# design-1v1.net
KiCad netlist of a schematic drawn in EAGLE
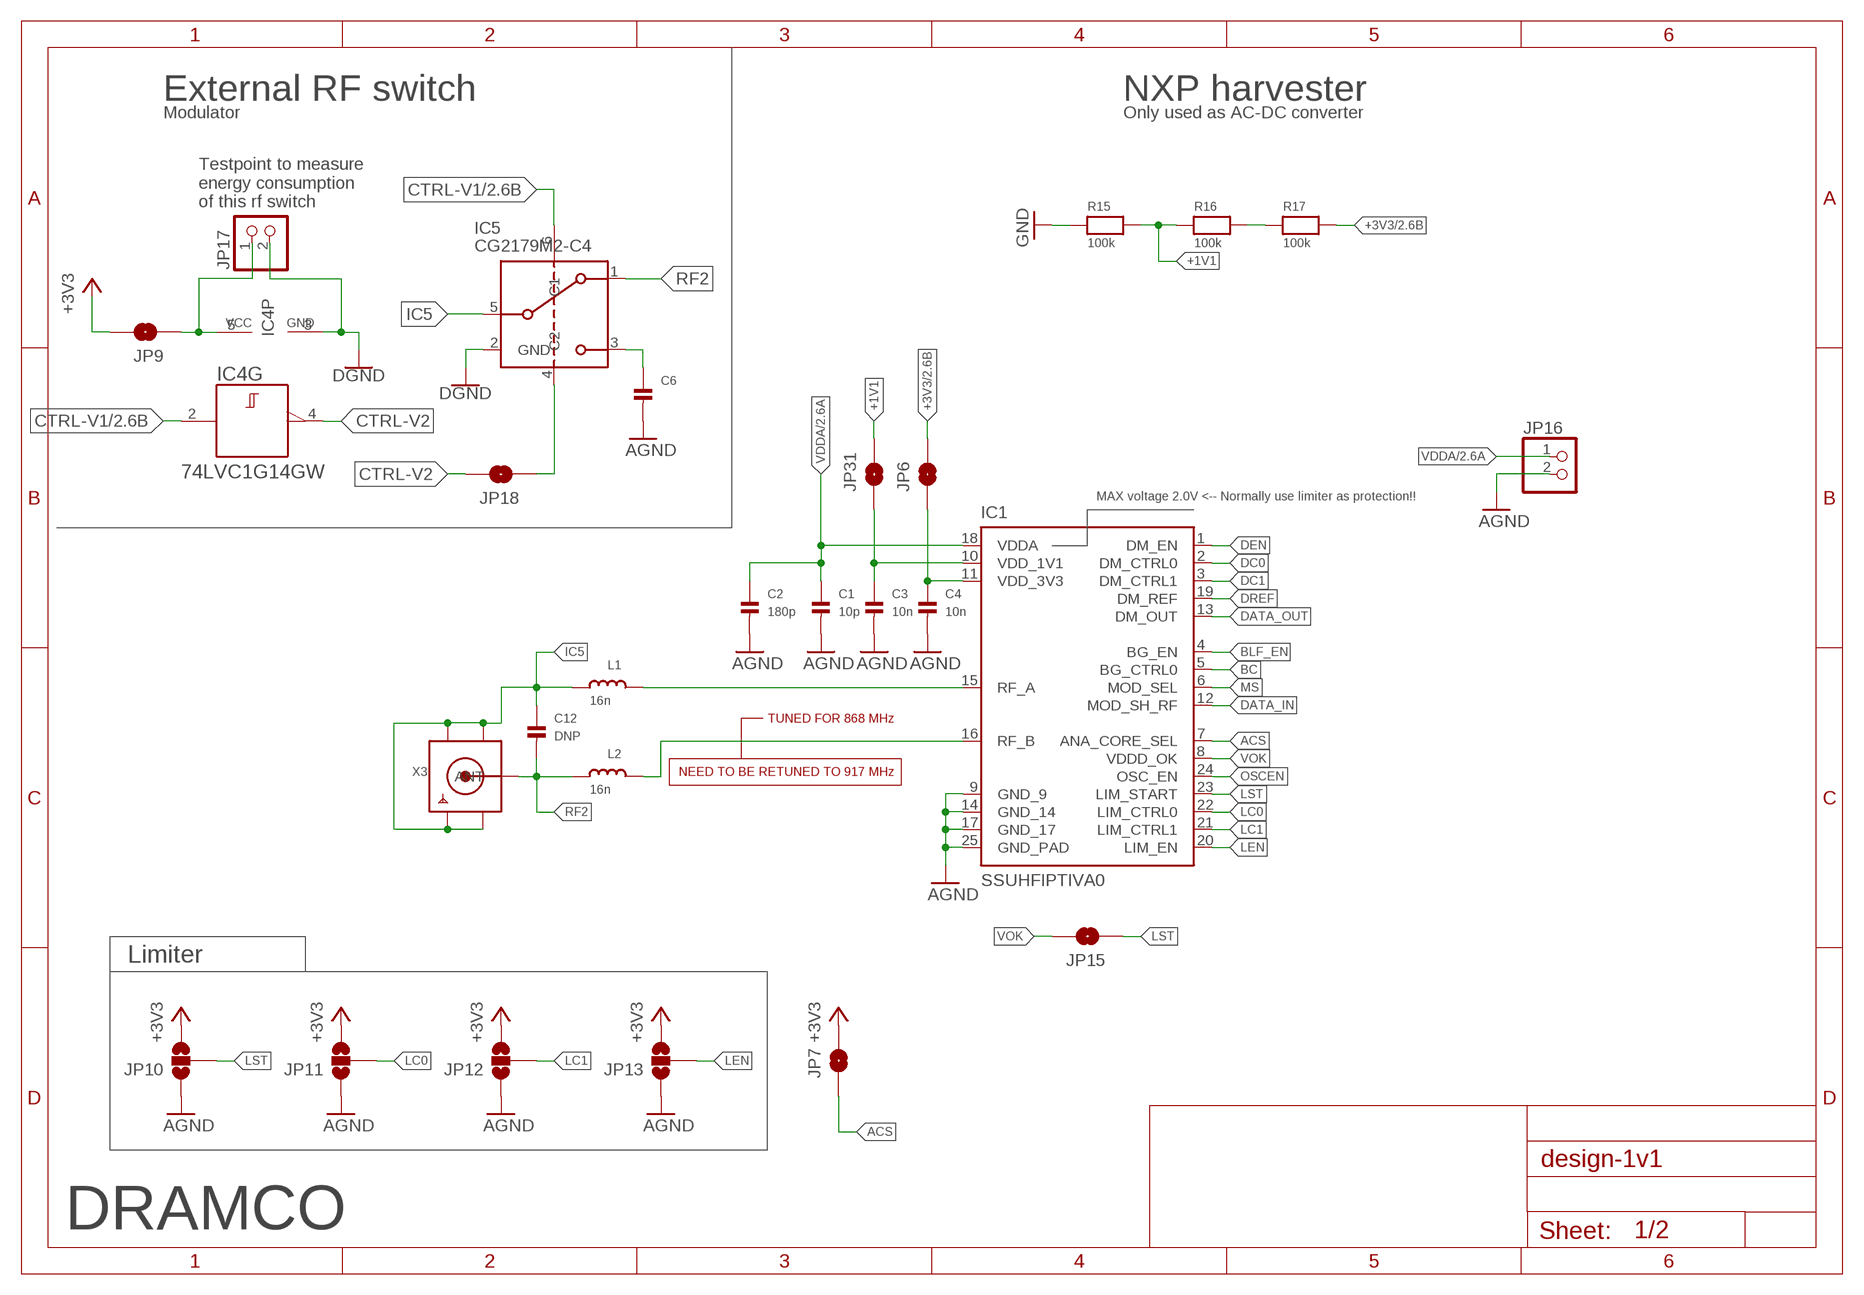
[diagram p0: schematic, sheet 1]
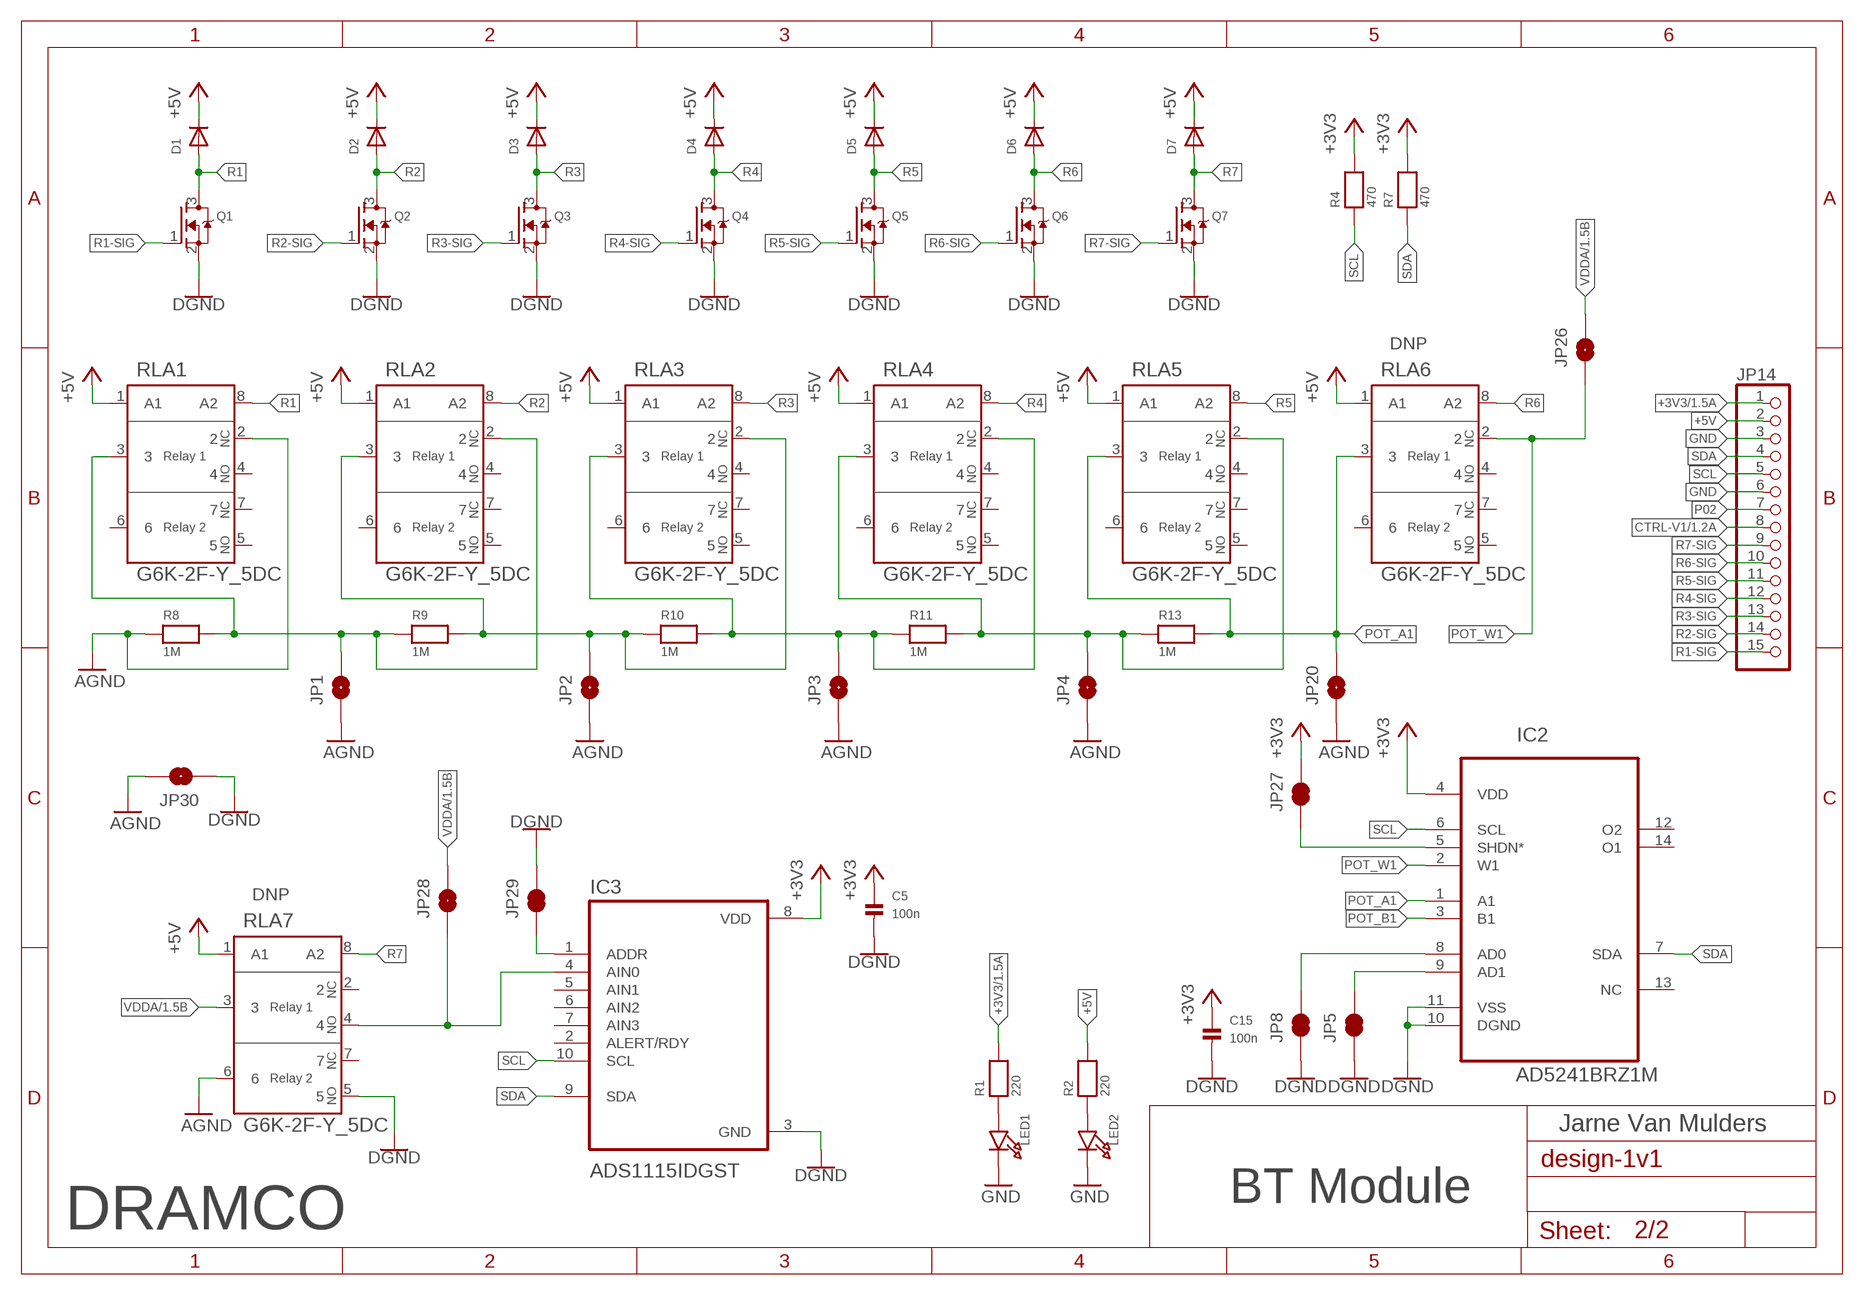
[diagram p1: schematic, sheet 2]

(export (version "E")
  (design (tool "Eeschema 10.0.6"))
  (components
    (comp (ref "C5")
      (value "100n")
      (footprint "eagle-import:0603")
      (libsource (lib "eagle-import") (part "CAP_CERAMIC0603"))
    )
    (comp (ref "C15")
      (value "100n")
      (footprint "eagle-import:0603")
      (libsource (lib "eagle-import") (part "CAP_CERAMIC0603"))
    )
    (comp (ref "D1")
      (value "DIODESOD-123")
      (footprint "eagle-import:SOD-123")
      (libsource (lib "eagle-import") (part "DIODESOD-123"))
    )
    (comp (ref "D2")
      (value "DIODESOD-123")
      (footprint "eagle-import:SOD-123")
      (libsource (lib "eagle-import") (part "DIODESOD-123"))
    )
    (comp (ref "D3")
      (value "DIODESOD-123")
      (footprint "eagle-import:SOD-123")
      (libsource (lib "eagle-import") (part "DIODESOD-123"))
    )
    (comp (ref "D4")
      (value "DIODESOD-123")
      (footprint "eagle-import:SOD-123")
      (libsource (lib "eagle-import") (part "DIODESOD-123"))
    )
    (comp (ref "D5")
      (value "DIODESOD-123")
      (footprint "eagle-import:SOD-123")
      (libsource (lib "eagle-import") (part "DIODESOD-123"))
    )
    (comp (ref "D6")
      (value "DIODESOD-123")
      (footprint "eagle-import:SOD-123")
      (libsource (lib "eagle-import") (part "DIODESOD-123"))
    )
    (comp (ref "D7")
      (value "DIODESOD-123")
      (footprint "eagle-import:SOD-123")
      (libsource (lib "eagle-import") (part "DIODESOD-123"))
    )
    (comp (ref "IC2")
      (value "AD5241BRZ1M")
      (footprint "eagle-import:SOIC127P600X175-14N")
      (fields (field (name "MF") "Analog Devices"))
      (libsource (lib "eagle-import") (part "AD5241BRZ1M"))
    )
    (comp (ref "IC3")
      (value "ADS1115IDGST")
      (footprint "eagle-import:SOP50P490X110-10N")
      (fields (field (name "MF") "Texas Instruments"))
      (libsource (lib "eagle-import") (part "ADS1115IDGST"))
    )
    (comp (ref "JP1")
      (value "JUMPER-SMT_2_NO_NO-SILK")
      (footprint "eagle-import:SMT-JUMPER_2_NO_NO-SILK")
      (libsource (lib "eagle-import") (part "JUMPER-SMT_2_NO_NO-SILK"))
    )
    (comp (ref "JP2")
      (value "JUMPER-SMT_2_NO_NO-SILK")
      (footprint "eagle-import:SMT-JUMPER_2_NO_NO-SILK")
      (libsource (lib "eagle-import") (part "JUMPER-SMT_2_NO_NO-SILK"))
    )
    (comp (ref "JP3")
      (value "JUMPER-SMT_2_NO_NO-SILK")
      (footprint "eagle-import:SMT-JUMPER_2_NO_NO-SILK")
      (libsource (lib "eagle-import") (part "JUMPER-SMT_2_NO_NO-SILK"))
    )
    (comp (ref "JP4")
      (value "JUMPER-SMT_2_NO_NO-SILK")
      (footprint "eagle-import:SMT-JUMPER_2_NO_NO-SILK")
      (libsource (lib "eagle-import") (part "JUMPER-SMT_2_NO_NO-SILK"))
    )
    (comp (ref "JP5")
      (value "JUMPER-SMT_2_NC_TRACE_NO-SILK")
      (footprint "eagle-import:SMT-JUMPER_2_NC_TRACE_NO-SILK")
      (libsource (lib "eagle-import") (part "JUMPER-SMT_2_NC_TRACE_NO-SILK"))
    )
    (comp (ref "JP8")
      (value "JUMPER-SMT_2_NC_TRACE_NO-SILK")
      (footprint "eagle-import:SMT-JUMPER_2_NC_TRACE_NO-SILK")
      (libsource (lib "eagle-import") (part "JUMPER-SMT_2_NC_TRACE_NO-SILK"))
    )
    (comp (ref "JP14")
      (value "HEADER-1X15")
      (footprint "eagle-import:1X15_ROUND_70")
      (libsource (lib "eagle-import") (part "HEADER-1X15"))
    )
    (comp (ref "JP20")
      (value "JUMPER-SMT_2_NO_NO-SILK")
      (footprint "eagle-import:SMT-JUMPER_2_NO_NO-SILK")
      (libsource (lib "eagle-import") (part "JUMPER-SMT_2_NO_NO-SILK"))
    )
    (comp (ref "JP26")
      (value "JUMPER-SMT_2_NO_NO-SILK")
      (footprint "eagle-import:SMT-JUMPER_2_NO_NO-SILK")
      (libsource (lib "eagle-import") (part "JUMPER-SMT_2_NO_NO-SILK"))
    )
    (comp (ref "JP27")
      (value "JUMPER-SMT_2_NC_TRACE_NO-SILK")
      (footprint "eagle-import:SMT-JUMPER_2_NC_TRACE_NO-SILK")
      (libsource (lib "eagle-import") (part "JUMPER-SMT_2_NC_TRACE_NO-SILK"))
    )
    (comp (ref "JP28")
      (value "JUMPER-SMT_2_NO_NO-SILK")
      (footprint "eagle-import:SMT-JUMPER_2_NO_NO-SILK")
      (libsource (lib "eagle-import") (part "JUMPER-SMT_2_NO_NO-SILK"))
    )
    (comp (ref "JP29")
      (value "JUMPER-SMT_2_NC_TRACE_NO-SILK")
      (footprint "eagle-import:SMT-JUMPER_2_NC_TRACE_NO-SILK")
      (libsource (lib "eagle-import") (part "JUMPER-SMT_2_NC_TRACE_NO-SILK"))
    )
    (comp (ref "JP30")
      (value "JUMPER-SMT_2_NO_NO-SILK")
      (footprint "eagle-import:SMT-JUMPER_2_NO_NO-SILK")
      (libsource (lib "eagle-import") (part "JUMPER-SMT_2_NO_NO-SILK"))
    )
    (comp (ref "LED1")
      (value "LED0805")
      (footprint "eagle-import:CHIPLED_0805")
      (libsource (lib "eagle-import") (part "LED0805"))
    )
    (comp (ref "LED2")
      (value "LED0805")
      (footprint "eagle-import:CHIPLED_0805")
      (libsource (lib "eagle-import") (part "LED0805"))
    )
    (comp (ref "Q1")
      (value "MOSFET-NREFLOW")
      (footprint "eagle-import:SOT23-R")
      (libsource (lib "eagle-import") (part "MOSFET-NREFLOW"))
    )
    (comp (ref "Q2")
      (value "MOSFET-NREFLOW")
      (footprint "eagle-import:SOT23-R")
      (libsource (lib "eagle-import") (part "MOSFET-NREFLOW"))
    )
    (comp (ref "Q3")
      (value "MOSFET-NREFLOW")
      (footprint "eagle-import:SOT23-R")
      (libsource (lib "eagle-import") (part "MOSFET-NREFLOW"))
    )
    (comp (ref "Q4")
      (value "MOSFET-NREFLOW")
      (footprint "eagle-import:SOT23-R")
      (libsource (lib "eagle-import") (part "MOSFET-NREFLOW"))
    )
    (comp (ref "Q5")
      (value "MOSFET-NREFLOW")
      (footprint "eagle-import:SOT23-R")
      (libsource (lib "eagle-import") (part "MOSFET-NREFLOW"))
    )
    (comp (ref "Q6")
      (value "MOSFET-NREFLOW")
      (footprint "eagle-import:SOT23-R")
      (libsource (lib "eagle-import") (part "MOSFET-NREFLOW"))
    )
    (comp (ref "Q7")
      (value "MOSFET-NREFLOW")
      (footprint "eagle-import:SOT23-R")
      (libsource (lib "eagle-import") (part "MOSFET-NREFLOW"))
    )
    (comp (ref "R1")
      (value "220")
      (footprint "eagle-import:0603")
      (libsource (lib "eagle-import") (part "RESISTOR0603"))
    )
    (comp (ref "R2")
      (value "220")
      (footprint "eagle-import:0603")
      (libsource (lib "eagle-import") (part "RESISTOR0603"))
    )
    (comp (ref "R4")
      (value "470")
      (footprint "eagle-import:0603")
      (libsource (lib "eagle-import") (part "RESISTOR0603"))
    )
    (comp (ref "R7")
      (value "470")
      (footprint "eagle-import:0603")
      (libsource (lib "eagle-import") (part "RESISTOR0603"))
    )
    (comp (ref "R8")
      (value "1M")
      (footprint "eagle-import:0805")
      (libsource (lib "eagle-import") (part "RESISTOR0805"))
    )
    (comp (ref "R9")
      (value "1M")
      (footprint "eagle-import:0805")
      (libsource (lib "eagle-import") (part "RESISTOR0805"))
    )
    (comp (ref "R10")
      (value "1M")
      (footprint "eagle-import:0805")
      (libsource (lib "eagle-import") (part "RESISTOR0805"))
    )
    (comp (ref "R11")
      (value "1M")
      (footprint "eagle-import:0805")
      (libsource (lib "eagle-import") (part "RESISTOR0805"))
    )
    (comp (ref "R13")
      (value "1M")
      (footprint "eagle-import:0805")
      (libsource (lib "eagle-import") (part "RESISTOR0805"))
    )
    (comp (ref "RLA1")
      (value "G6K-2F-Y_5DC")
      (footprint "eagle-import:RELAY_G6K-2F_OMR")
      (fields
        (field (name "MANUFACTURER_PART_NUMBER") "G6K-2F-Y 5DC")
        (field (name "COPYRIGHT") "Copyright (C) 2024 Ultra Librarian. All rights reserved.")
      )
      (libsource (lib "eagle-import") (part "G6K-2F-Y_5DC"))
    )
    (comp (ref "RLA2")
      (value "G6K-2F-Y_5DC")
      (footprint "eagle-import:RELAY_G6K-2F_OMR")
      (fields
        (field (name "MANUFACTURER_PART_NUMBER") "G6K-2F-Y 5DC")
        (field (name "COPYRIGHT") "Copyright (C) 2024 Ultra Librarian. All rights reserved.")
      )
      (libsource (lib "eagle-import") (part "G6K-2F-Y_5DC"))
    )
    (comp (ref "RLA3")
      (value "G6K-2F-Y_5DC")
      (footprint "eagle-import:RELAY_G6K-2F_OMR")
      (fields
        (field (name "MANUFACTURER_PART_NUMBER") "G6K-2F-Y 5DC")
        (field (name "COPYRIGHT") "Copyright (C) 2024 Ultra Librarian. All rights reserved.")
      )
      (libsource (lib "eagle-import") (part "G6K-2F-Y_5DC"))
    )
    (comp (ref "RLA4")
      (value "G6K-2F-Y_5DC")
      (footprint "eagle-import:RELAY_G6K-2F_OMR")
      (fields
        (field (name "MANUFACTURER_PART_NUMBER") "G6K-2F-Y 5DC")
        (field (name "COPYRIGHT") "Copyright (C) 2024 Ultra Librarian. All rights reserved.")
      )
      (libsource (lib "eagle-import") (part "G6K-2F-Y_5DC"))
    )
    (comp (ref "RLA5")
      (value "G6K-2F-Y_5DC")
      (footprint "eagle-import:RELAY_G6K-2F_OMR")
      (fields
        (field (name "MANUFACTURER_PART_NUMBER") "G6K-2F-Y 5DC")
        (field (name "COPYRIGHT") "Copyright (C) 2024 Ultra Librarian. All rights reserved.")
      )
      (libsource (lib "eagle-import") (part "G6K-2F-Y_5DC"))
    )
    (comp (ref "RLA6")
      (value "G6K-2F-Y_5DC")
      (footprint "eagle-import:RELAY_G6K-2F_OMR")
      (fields
        (field (name "MANUFACTURER_PART_NUMBER") "G6K-2F-Y 5DC")
        (field (name "COPYRIGHT") "Copyright (C) 2024 Ultra Librarian. All rights reserved.")
      )
      (libsource (lib "eagle-import") (part "G6K-2F-Y_5DC"))
    )
    (comp (ref "RLA7")
      (value "G6K-2F-Y_5DC")
      (footprint "eagle-import:RELAY_G6K-2F_OMR")
      (fields
        (field (name "MANUFACTURER_PART_NUMBER") "G6K-2F-Y 5DC")
        (field (name "COPYRIGHT") "Copyright (C) 2024 Ultra Librarian. All rights reserved.")
      )
      (libsource (lib "eagle-import") (part "G6K-2F-Y_5DC"))
    )
    (comp (ref "C1")
      (value "10p")
      (footprint "eagle-import:0603")
      (libsource (lib "eagle-import") (part "CAP_CERAMIC0603"))
    )
    (comp (ref "C2")
      (value "180p")
      (footprint "eagle-import:0603")
      (libsource (lib "eagle-import") (part "CAP_CERAMIC0603"))
    )
    (comp (ref "C3")
      (value "10n")
      (footprint "eagle-import:0603")
      (libsource (lib "eagle-import") (part "CAP_CERAMIC0603"))
    )
    (comp (ref "C4")
      (value "10n")
      (footprint "eagle-import:0603")
      (libsource (lib "eagle-import") (part "CAP_CERAMIC0603"))
    )
    (comp (ref "C6")
      (value "CAP_CERAMIC0402")
      (footprint "eagle-import:0402")
      (libsource (lib "eagle-import") (part "CAP_CERAMIC0402"))
    )
    (comp (ref "C12")
      (value "DNP")
      (footprint "eagle-import:0402")
      (libsource (lib "eagle-import") (part "CAP_CERAMIC0402"))
    )
    (comp (ref "IC1")
      (value "SSUHFIPTIVA0")
      (footprint "eagle-import:QFN50P400X400X90-25N")
      (libsource (lib "eagle-import") (part "SSUHFIPTIVA0"))
    )
    (comp (ref "IC4")
      (value "74LVC1G14GW")
      (footprint "eagle-import:SOT353-1")
      (libsource (lib "eagle-import") (part "74LVC1G14GW"))
    )
    (comp (ref "IC5")
      (value "CG2179M2-C4")
      (footprint "eagle-import:SC70-6-CNC04")
      (fields (field (name "MF") "CEL"))
      (libsource (lib "eagle-import") (part "CG2179M2-C4"))
    )
    (comp (ref "JP6")
      (value "JUMPER-SMT_2_NO_NO-SILK")
      (footprint "eagle-import:SMT-JUMPER_2_NO_NO-SILK")
      (libsource (lib "eagle-import") (part "JUMPER-SMT_2_NO_NO-SILK"))
    )
    (comp (ref "JP7")
      (value "JUMPER-SMT_2_NO_NO-SILK")
      (footprint "eagle-import:SMT-JUMPER_2_NO_NO-SILK")
      (libsource (lib "eagle-import") (part "JUMPER-SMT_2_NO_NO-SILK"))
    )
    (comp (ref "JP9")
      (value "JUMPER-SMT_2_NO_NO-SILK")
      (footprint "eagle-import:SMT-JUMPER_2_NO_NO-SILK")
      (libsource (lib "eagle-import") (part "JUMPER-SMT_2_NO_NO-SILK"))
    )
    (comp (ref "JP10")
      (value "JUMPER-SMT_3_NO_SILK")
      (footprint "eagle-import:SMT-JUMPER_3_NO_SILK")
      (libsource (lib "eagle-import") (part "JUMPER-SMT_3_NO_SILK"))
    )
    (comp (ref "JP11")
      (value "JUMPER-SMT_3_NO_SILK")
      (footprint "eagle-import:SMT-JUMPER_3_NO_SILK")
      (libsource (lib "eagle-import") (part "JUMPER-SMT_3_NO_SILK"))
    )
    (comp (ref "JP12")
      (value "JUMPER-SMT_3_NO_SILK")
      (footprint "eagle-import:SMT-JUMPER_3_NO_SILK")
      (libsource (lib "eagle-import") (part "JUMPER-SMT_3_NO_SILK"))
    )
    (comp (ref "JP13")
      (value "JUMPER-SMT_3_NO_SILK")
      (footprint "eagle-import:SMT-JUMPER_3_NO_SILK")
      (libsource (lib "eagle-import") (part "JUMPER-SMT_3_NO_SILK"))
    )
    (comp (ref "JP15")
      (value "JUMPER-SMT_2_NO_NO-SILK")
      (footprint "eagle-import:SMT-JUMPER_2_NO_NO-SILK")
      (libsource (lib "eagle-import") (part "JUMPER-SMT_2_NO_NO-SILK"))
    )
    (comp (ref "JP16")
      (value "HEADER-1X2ROUND")
      (footprint "eagle-import:1X02_ROUND")
      (libsource (lib "eagle-import") (part "HEADER-1X2ROUND"))
    )
    (comp (ref "JP17")
      (value "HEADER-1X2ROUND")
      (footprint "eagle-import:1X02_ROUND")
      (libsource (lib "eagle-import") (part "HEADER-1X2ROUND"))
    )
    (comp (ref "JP18")
      (value "JUMPER-SMT_2_NO_NO-SILK")
      (footprint "eagle-import:SMT-JUMPER_2_NO_NO-SILK")
      (libsource (lib "eagle-import") (part "JUMPER-SMT_2_NO_NO-SILK"))
    )
    (comp (ref "JP31")
      (value "JUMPER-SMT_2_NO_NO-SILK")
      (footprint "eagle-import:SMT-JUMPER_2_NO_NO-SILK")
      (libsource (lib "eagle-import") (part "JUMPER-SMT_2_NO_NO-SILK"))
    )
    (comp (ref "L1")
      (value "16n")
      (footprint "eagle-import:_0402")
      (libsource (lib "eagle-import") (part "INDUCTOR_0402"))
    )
    (comp (ref "L2")
      (value "16n")
      (footprint "eagle-import:_0402")
      (libsource (lib "eagle-import") (part "INDUCTOR_0402"))
    )
    (comp (ref "R15")
      (value "100k")
      (footprint "eagle-import:0603")
      (libsource (lib "eagle-import") (part "RESISTOR0603"))
    )
    (comp (ref "R16")
      (value "100k")
      (footprint "eagle-import:0603")
      (libsource (lib "eagle-import") (part "RESISTOR0603"))
    )
    (comp (ref "R17")
      (value "100k")
      (footprint "eagle-import:0603")
      (libsource (lib "eagle-import") (part "RESISTOR0603"))
    )
    (comp (ref "X3")
      (value "SMACONNECTOR_EDGE_UFL")
      (footprint "eagle-import:SMA_EDGELAUNCH_UFL")
      (libsource (lib "eagle-import") (part "SMACONNECTOR_EDGE_UFL"))
    )
  )
  (nets
    (net (code "1") (name "+1V1") (class "Default")
      (node (ref "JP31") (pin "2") (pinfunction "2_2") (pintype "passive"))
      (node (ref "R15") (pin "2") (pinfunction "2_2") (pintype "passive"))
      (node (ref "R16") (pin "1") (pinfunction "1_1") (pintype "passive"))
    )
    (net (code "2") (name "+3V3") (class "Default")
      (node (ref "C15") (pin "1") (pinfunction "P$1_1") (pintype "passive"))
      (node (ref "C5") (pin "1") (pinfunction "P$1_1") (pintype "passive"))
      (node (ref "IC2") (pin "4") (pinfunction "VDD_4") (pintype "power_in"))
      (node (ref "IC3") (pin "8") (pinfunction "VDD_8") (pintype "power_in"))
      (node (ref "JP10") (pin "3") (pinfunction "3_3") (pintype "passive"))
      (node (ref "JP11") (pin "3") (pinfunction "3_3") (pintype "passive"))
      (node (ref "JP12") (pin "3") (pinfunction "3_3") (pintype "passive"))
      (node (ref "JP13") (pin "3") (pinfunction "3_3") (pintype "passive"))
      (node (ref "JP14") (pin "1") (pinfunction "1_1") (pintype "passive"))
      (node (ref "JP27") (pin "2") (pinfunction "2_2") (pintype "passive"))
      (node (ref "JP6") (pin "2") (pinfunction "2_2") (pintype "passive"))
      (node (ref "JP7") (pin "2") (pinfunction "2_2") (pintype "passive"))
      (node (ref "JP9") (pin "2") (pinfunction "2_2") (pintype "passive"))
      (node (ref "R1") (pin "2") (pinfunction "2_2") (pintype "passive"))
      (node (ref "R17") (pin "2") (pinfunction "2_2") (pintype "passive"))
      (node (ref "R4") (pin "2") (pinfunction "2_2") (pintype "passive"))
      (node (ref "R7") (pin "2") (pinfunction "2_2") (pintype "passive"))
    )
    (net (code "3") (name "+5V") (class "Default")
      (node (ref "D1") (pin "C") (pinfunction "C_C") (pintype "passive"))
      (node (ref "D2") (pin "C") (pinfunction "C_C") (pintype "passive"))
      (node (ref "D3") (pin "C") (pinfunction "C_C") (pintype "passive"))
      (node (ref "D4") (pin "C") (pinfunction "C_C") (pintype "passive"))
      (node (ref "D5") (pin "C") (pinfunction "C_C") (pintype "passive"))
      (node (ref "D6") (pin "C") (pinfunction "C_C") (pintype "passive"))
      (node (ref "D7") (pin "C") (pinfunction "C_C") (pintype "passive"))
      (node (ref "JP14") (pin "2") (pinfunction "2_2") (pintype "passive"))
      (node (ref "R2") (pin "2") (pinfunction "2_2") (pintype "passive"))
      (node (ref "RLA1") (pin "1") (pinfunction "A1_1") (pintype "passive"))
      (node (ref "RLA2") (pin "1") (pinfunction "A1_1") (pintype "passive"))
      (node (ref "RLA3") (pin "1") (pinfunction "A1_1") (pintype "passive"))
      (node (ref "RLA4") (pin "1") (pinfunction "A1_1") (pintype "passive"))
      (node (ref "RLA5") (pin "1") (pinfunction "A1_1") (pintype "passive"))
      (node (ref "RLA6") (pin "1") (pinfunction "A1_1") (pintype "passive"))
      (node (ref "RLA7") (pin "1") (pinfunction "A1_1") (pintype "passive"))
    )
    (net (code "4") (name "ACS") (class "Default")
      (node (ref "IC1") (pin "7") (pinfunction "ANA_CORE_SEL_7") (pintype "bidirectional"))
      (node (ref "JP7") (pin "1") (pinfunction "1_1") (pintype "passive"))
    )
    (net (code "5") (name "AGND") (class "Default")
      (node (ref "C1") (pin "2") (pinfunction "P$2_2") (pintype "passive"))
      (node (ref "C2") (pin "2") (pinfunction "P$2_2") (pintype "passive"))
      (node (ref "C3") (pin "2") (pinfunction "P$2_2") (pintype "passive"))
      (node (ref "C4") (pin "2") (pinfunction "P$2_2") (pintype "passive"))
      (node (ref "C6") (pin "2") (pinfunction "P$2_2") (pintype "passive"))
      (node (ref "IC1") (pin "14") (pinfunction "GND_14_14") (pintype "bidirectional"))
      (node (ref "IC1") (pin "17") (pinfunction "GND_17_17") (pintype "bidirectional"))
      (node (ref "IC1") (pin "25") (pinfunction "GND_PAD_25") (pintype "bidirectional"))
      (node (ref "IC1") (pin "9") (pinfunction "GND_9_9") (pintype "bidirectional"))
      (node (ref "JP1") (pin "1") (pinfunction "1_1") (pintype "passive"))
      (node (ref "JP10") (pin "1") (pinfunction "1_1") (pintype "passive"))
      (node (ref "JP11") (pin "1") (pinfunction "1_1") (pintype "passive"))
      (node (ref "JP12") (pin "1") (pinfunction "1_1") (pintype "passive"))
      (node (ref "JP13") (pin "1") (pinfunction "1_1") (pintype "passive"))
      (node (ref "JP16") (pin "2") (pinfunction "2_2") (pintype "passive"))
      (node (ref "JP2") (pin "1") (pinfunction "1_1") (pintype "passive"))
      (node (ref "JP20") (pin "1") (pinfunction "1_1") (pintype "passive"))
      (node (ref "JP3") (pin "1") (pinfunction "1_1") (pintype "passive"))
      (node (ref "JP30") (pin "2") (pinfunction "2_2") (pintype "passive"))
      (node (ref "JP4") (pin "1") (pinfunction "1_1") (pintype "passive"))
      (node (ref "R8") (pin "1") (pinfunction "1_1") (pintype "passive"))
      (node (ref "RLA1") (pin "2") (pinfunction "2_2") (pintype "passive"))
      (node (ref "RLA7") (pin "6") (pinfunction "6_6") (pintype "passive"))
    )
    (net (code "6") (name "BC") (class "Default")
      (node (ref "IC1") (pin "5") (pinfunction "BG_CTRL0_5") (pintype "bidirectional"))
    )
    (net (code "7") (name "BLF_EN") (class "Default")
      (node (ref "IC1") (pin "4") (pinfunction "BG_EN_4") (pintype "bidirectional"))
    )
    (net (code "8") (name "CTRL-V1") (class "Default")
      (node (ref "IC4") (pin "2") (pinfunction "A_2") (pintype "input"))
      (node (ref "IC5") (pin "6") (pinfunction "C1_6") (pintype "bidirectional"))
      (node (ref "JP14") (pin "8") (pinfunction "8_8") (pintype "passive"))
    )
    (net (code "9") (name "CTRL-V2") (class "Default")
      (node (ref "IC4") (pin "4") (pinfunction "Y_4") (pintype "output"))
      (node (ref "JP18") (pin "2") (pinfunction "2_2") (pintype "passive"))
    )
    (net (code "10") (name "DATA_IN") (class "Default")
      (node (ref "IC1") (pin "12") (pinfunction "MOD_SH_RF_12") (pintype "bidirectional"))
    )
    (net (code "11") (name "DATA_OUT") (class "Default")
      (node (ref "IC1") (pin "13") (pinfunction "DM_OUT_13") (pintype "bidirectional"))
    )
    (net (code "12") (name "DC0") (class "Default")
      (node (ref "IC1") (pin "2") (pinfunction "DM_CTRL0_2") (pintype "bidirectional"))
    )
    (net (code "13") (name "DC1") (class "Default")
      (node (ref "IC1") (pin "3") (pinfunction "DM_CTRL1_3") (pintype "bidirectional"))
    )
    (net (code "14") (name "DEN") (class "Default")
      (node (ref "IC1") (pin "1") (pinfunction "DM_EN_1") (pintype "bidirectional"))
    )
    (net (code "15") (name "DREF") (class "Default")
      (node (ref "IC1") (pin "19") (pinfunction "DM_REF_19") (pintype "bidirectional"))
    )
    (net (code "16") (name "GND") (class "Default")
      (node (ref "C15") (pin "2") (pinfunction "P$2_2") (pintype "passive"))
      (node (ref "C5") (pin "2") (pinfunction "P$2_2") (pintype "passive"))
      (node (ref "IC2") (pin "10") (pinfunction "DGND_10") (pintype "passive"))
      (node (ref "IC2") (pin "11") (pinfunction "VSS_11") (pintype "power_in"))
      (node (ref "IC3") (pin "3") (pinfunction "GND_3") (pintype "power_in"))
      (node (ref "IC4") (pin "3") (pinfunction "GND_3") (pintype "power_in"))
      (node (ref "IC5") (pin "2") (pinfunction "GND_2") (pintype "bidirectional"))
      (node (ref "JP14") (pin "3") (pinfunction "3_3") (pintype "passive"))
      (node (ref "JP14") (pin "6") (pinfunction "6_6") (pintype "passive"))
      (node (ref "JP17") (pin "2") (pinfunction "2_2") (pintype "passive"))
      (node (ref "JP29") (pin "2") (pinfunction "2_2") (pintype "passive"))
      (node (ref "JP30") (pin "1") (pinfunction "1_1") (pintype "passive"))
      (node (ref "JP5") (pin "1") (pinfunction "1_1") (pintype "passive"))
      (node (ref "JP8") (pin "1") (pinfunction "1_1") (pintype "passive"))
      (node (ref "LED1") (pin "C") (pinfunction "C_C") (pintype "passive"))
      (node (ref "LED2") (pin "C") (pinfunction "C_C") (pintype "passive"))
      (node (ref "Q1") (pin "2") (pinfunction "S_2") (pintype "bidirectional"))
      (node (ref "Q2") (pin "2") (pinfunction "S_2") (pintype "bidirectional"))
      (node (ref "Q3") (pin "2") (pinfunction "S_2") (pintype "bidirectional"))
      (node (ref "Q4") (pin "2") (pinfunction "S_2") (pintype "bidirectional"))
      (node (ref "Q5") (pin "2") (pinfunction "S_2") (pintype "bidirectional"))
      (node (ref "Q6") (pin "2") (pinfunction "S_2") (pintype "bidirectional"))
      (node (ref "Q7") (pin "2") (pinfunction "S_2") (pintype "bidirectional"))
      (node (ref "R15") (pin "1") (pinfunction "1_1") (pintype "passive"))
      (node (ref "RLA7") (pin "5") (pinfunction "5_5") (pintype "passive"))
    )
    (net (code "17") (name "IC5") (class "Default")
      (node (ref "C12") (pin "1") (pinfunction "P$1_1") (pintype "passive"))
      (node (ref "IC5") (pin "5") (pinfunction "PC_5") (pintype "bidirectional"))
      (node (ref "L1") (pin "1") (pinfunction "1_1") (pintype "passive"))
      (node (ref "X3") (pin "GND@1") (pinfunction "GND1_GND@1") (pintype "power_in"))
      (node (ref "X3") (pin "GND@2") (pinfunction "GND2_GND@2") (pintype "power_in"))
      (node (ref "X3") (pin "GND@3") (pinfunction "GND3_GND@3") (pintype "power_in"))
      (node (ref "X3") (pin "GND@4") (pinfunction "GND4_GND@4") (pintype "power_in"))
    )
    (net (code "18") (name "LC0") (class "Default")
      (node (ref "IC1") (pin "22") (pinfunction "LIM_CTRL0_22") (pintype "bidirectional"))
      (node (ref "JP11") (pin "2") (pinfunction "2_2") (pintype "passive"))
    )
    (net (code "19") (name "LC1") (class "Default")
      (node (ref "IC1") (pin "21") (pinfunction "LIM_CTRL1_21") (pintype "bidirectional"))
      (node (ref "JP12") (pin "2") (pinfunction "2_2") (pintype "passive"))
    )
    (net (code "20") (name "LEN") (class "Default")
      (node (ref "IC1") (pin "20") (pinfunction "LIM_EN_20") (pintype "bidirectional"))
      (node (ref "JP13") (pin "2") (pinfunction "2_2") (pintype "passive"))
    )
    (net (code "21") (name "LST") (class "Default")
      (node (ref "IC1") (pin "23") (pinfunction "LIM_START_23") (pintype "bidirectional"))
      (node (ref "JP10") (pin "2") (pinfunction "2_2") (pintype "passive"))
      (node (ref "JP15") (pin "1") (pinfunction "1_1") (pintype "passive"))
    )
    (net (code "22") (name "MS") (class "Default")
      (node (ref "IC1") (pin "6") (pinfunction "MOD_SEL_6") (pintype "bidirectional"))
    )
    (net (code "23") (name "Net-(C3-P$1)") (class "Default")
      (node (ref "C3") (pin "1") (pinfunction "P$1_1") (pintype "passive"))
      (node (ref "IC1") (pin "10") (pinfunction "VDD_1V1_10") (pintype "bidirectional"))
      (node (ref "JP31") (pin "1") (pinfunction "1_1") (pintype "passive"))
    )
    (net (code "24") (name "Net-(C4-P$1)") (class "Default")
      (node (ref "C4") (pin "1") (pinfunction "P$1_1") (pintype "passive"))
      (node (ref "IC1") (pin "11") (pinfunction "VDD_3V3_11") (pintype "bidirectional"))
      (node (ref "JP6") (pin "1") (pinfunction "1_1") (pintype "passive"))
    )
    (net (code "25") (name "Net-(C6-P$1)") (class "Default")
      (node (ref "C6") (pin "1") (pinfunction "P$1_1") (pintype "passive"))
      (node (ref "IC5") (pin "3") (pinfunction "P2_3") (pintype "bidirectional"))
    )
    (net (code "26") (name "Net-(IC1-RF_A)") (class "Default")
      (node (ref "IC1") (pin "15") (pinfunction "RF_A_15") (pintype "bidirectional"))
      (node (ref "L1") (pin "2") (pinfunction "2_2") (pintype "passive"))
    )
    (net (code "27") (name "Net-(IC1-RF_B)") (class "Default")
      (node (ref "IC1") (pin "16") (pinfunction "RF_B_16") (pintype "bidirectional"))
      (node (ref "L2") (pin "2") (pinfunction "2_2") (pintype "passive"))
    )
    (net (code "28") (name "Net-(IC2-AD0)") (class "Default")
      (node (ref "IC2") (pin "8") (pinfunction "AD0_8") (pintype "passive"))
      (node (ref "JP8") (pin "2") (pinfunction "2_2") (pintype "passive"))
    )
    (net (code "29") (name "Net-(IC2-AD1)") (class "Default")
      (node (ref "IC2") (pin "9") (pinfunction "AD1_9") (pintype "passive"))
      (node (ref "JP5") (pin "2") (pinfunction "2_2") (pintype "passive"))
    )
    (net (code "30") (name "Net-(IC2-SHDN*)") (class "Default")
      (node (ref "IC2") (pin "5") (pinfunction "SHDN*_5") (pintype "passive"))
      (node (ref "JP27") (pin "1") (pinfunction "1_1") (pintype "passive"))
    )
    (net (code "31") (name "Net-(IC3-ADDR)") (class "Default")
      (node (ref "IC3") (pin "1") (pinfunction "ADDR_1") (pintype "input"))
      (node (ref "JP29") (pin "1") (pinfunction "1_1") (pintype "passive"))
    )
    (net (code "32") (name "Net-(IC3-AIN0)") (class "Default")
      (node (ref "IC3") (pin "4") (pinfunction "AIN0_4") (pintype "input"))
      (node (ref "JP28") (pin "1") (pinfunction "1_1") (pintype "passive"))
      (node (ref "RLA7") (pin "4") (pinfunction "4_4") (pintype "passive"))
    )
    (net (code "33") (name "Net-(IC4B-VCC)") (class "Default")
      (node (ref "IC4") (pin "5") (pinfunction "VCC_5") (pintype "power_in"))
      (node (ref "JP17") (pin "1") (pinfunction "1_1") (pintype "passive"))
      (node (ref "JP9") (pin "1") (pinfunction "1_1") (pintype "passive"))
    )
    (net (code "34") (name "Net-(IC5-C2)") (class "Default")
      (node (ref "IC5") (pin "4") (pinfunction "C2_4") (pintype "bidirectional"))
      (node (ref "JP18") (pin "1") (pinfunction "1_1") (pintype "passive"))
    )
    (net (code "35") (name "Net-(JP1-Pad2)") (class "Default")
      (node (ref "JP1") (pin "2") (pinfunction "2_2") (pintype "passive"))
      (node (ref "R8") (pin "2") (pinfunction "2_2") (pintype "passive"))
      (node (ref "R9") (pin "1") (pinfunction "1_1") (pintype "passive"))
      (node (ref "RLA1") (pin "3") (pinfunction "3_3") (pintype "passive"))
      (node (ref "RLA2") (pin "2") (pinfunction "2_2") (pintype "passive"))
    )
    (net (code "36") (name "Net-(JP2-Pad2)") (class "Default")
      (node (ref "JP2") (pin "2") (pinfunction "2_2") (pintype "passive"))
      (node (ref "R10") (pin "1") (pinfunction "1_1") (pintype "passive"))
      (node (ref "R9") (pin "2") (pinfunction "2_2") (pintype "passive"))
      (node (ref "RLA2") (pin "3") (pinfunction "3_3") (pintype "passive"))
      (node (ref "RLA3") (pin "2") (pinfunction "2_2") (pintype "passive"))
    )
    (net (code "37") (name "Net-(JP3-Pad2)") (class "Default")
      (node (ref "JP3") (pin "2") (pinfunction "2_2") (pintype "passive"))
      (node (ref "R10") (pin "2") (pinfunction "2_2") (pintype "passive"))
      (node (ref "R11") (pin "1") (pinfunction "1_1") (pintype "passive"))
      (node (ref "RLA3") (pin "3") (pinfunction "3_3") (pintype "passive"))
      (node (ref "RLA4") (pin "2") (pinfunction "2_2") (pintype "passive"))
    )
    (net (code "38") (name "Net-(JP4-Pad2)") (class "Default")
      (node (ref "JP4") (pin "2") (pinfunction "2_2") (pintype "passive"))
      (node (ref "R11") (pin "2") (pinfunction "2_2") (pintype "passive"))
      (node (ref "R13") (pin "1") (pinfunction "1_1") (pintype "passive"))
      (node (ref "RLA4") (pin "3") (pinfunction "3_3") (pintype "passive"))
      (node (ref "RLA5") (pin "2") (pinfunction "2_2") (pintype "passive"))
    )
    (net (code "39") (name "Net-(LED1-PadA)") (class "Default")
      (node (ref "LED1") (pin "A") (pinfunction "A_A") (pintype "passive"))
      (node (ref "R1") (pin "1") (pinfunction "1_1") (pintype "passive"))
    )
    (net (code "40") (name "Net-(LED2-PadA)") (class "Default")
      (node (ref "LED2") (pin "A") (pinfunction "A_A") (pintype "passive"))
      (node (ref "R2") (pin "1") (pinfunction "1_1") (pintype "passive"))
    )
    (net (code "41") (name "Net-(R16-Pad2)") (class "Default")
      (node (ref "R16") (pin "2") (pinfunction "2_2") (pintype "passive"))
      (node (ref "R17") (pin "1") (pinfunction "1_1") (pintype "passive"))
    )
    (net (code "42") (name "OSCEN") (class "Default")
      (node (ref "IC1") (pin "24") (pinfunction "OSC_EN_24") (pintype "bidirectional"))
    )
    (net (code "43") (name "P02") (class "Default")
      (node (ref "JP14") (pin "7") (pinfunction "7_7") (pintype "passive"))
    )
    (net (code "44") (name "POT_A1") (class "Default")
      (node (ref "IC2") (pin "1") (pinfunction "A1_1") (pintype "passive"))
      (node (ref "JP20") (pin "2") (pinfunction "2_2") (pintype "passive"))
      (node (ref "R13") (pin "2") (pinfunction "2_2") (pintype "passive"))
      (node (ref "RLA5") (pin "3") (pinfunction "3_3") (pintype "passive"))
      (node (ref "RLA6") (pin "3") (pinfunction "3_3") (pintype "passive"))
    )
    (net (code "45") (name "POT_B1") (class "Default")
      (node (ref "IC2") (pin "3") (pinfunction "B1_3") (pintype "passive"))
    )
    (net (code "46") (name "POT_W1") (class "Default")
      (node (ref "IC2") (pin "2") (pinfunction "W1_2") (pintype "passive"))
      (node (ref "JP26") (pin "1") (pinfunction "1_1") (pintype "passive"))
      (node (ref "RLA6") (pin "2") (pinfunction "2_2") (pintype "passive"))
    )
    (net (code "47") (name "R1") (class "Default")
      (node (ref "D1") (pin "A") (pinfunction "A_A") (pintype "passive"))
      (node (ref "Q1") (pin "3") (pinfunction "D_3") (pintype "bidirectional"))
      (node (ref "RLA1") (pin "8") (pinfunction "A2_8") (pintype "passive"))
    )
    (net (code "48") (name "R1-SIG") (class "Default")
      (node (ref "JP14") (pin "15") (pinfunction "15_15") (pintype "passive"))
      (node (ref "Q1") (pin "1") (pinfunction "G_1") (pintype "bidirectional"))
    )
    (net (code "49") (name "R2") (class "Default")
      (node (ref "D2") (pin "A") (pinfunction "A_A") (pintype "passive"))
      (node (ref "Q2") (pin "3") (pinfunction "D_3") (pintype "bidirectional"))
      (node (ref "RLA2") (pin "8") (pinfunction "A2_8") (pintype "passive"))
    )
    (net (code "50") (name "R2-SIG") (class "Default")
      (node (ref "JP14") (pin "14") (pinfunction "14_14") (pintype "passive"))
      (node (ref "Q2") (pin "1") (pinfunction "G_1") (pintype "bidirectional"))
    )
    (net (code "51") (name "R3") (class "Default")
      (node (ref "D3") (pin "A") (pinfunction "A_A") (pintype "passive"))
      (node (ref "Q3") (pin "3") (pinfunction "D_3") (pintype "bidirectional"))
      (node (ref "RLA3") (pin "8") (pinfunction "A2_8") (pintype "passive"))
    )
    (net (code "52") (name "R3-SIG") (class "Default")
      (node (ref "JP14") (pin "13") (pinfunction "13_13") (pintype "passive"))
      (node (ref "Q3") (pin "1") (pinfunction "G_1") (pintype "bidirectional"))
    )
    (net (code "53") (name "R4") (class "Default")
      (node (ref "D4") (pin "A") (pinfunction "A_A") (pintype "passive"))
      (node (ref "Q4") (pin "3") (pinfunction "D_3") (pintype "bidirectional"))
      (node (ref "RLA4") (pin "8") (pinfunction "A2_8") (pintype "passive"))
    )
    (net (code "54") (name "R4-SIG") (class "Default")
      (node (ref "JP14") (pin "12") (pinfunction "12_12") (pintype "passive"))
      (node (ref "Q4") (pin "1") (pinfunction "G_1") (pintype "bidirectional"))
    )
    (net (code "55") (name "R5") (class "Default")
      (node (ref "D5") (pin "A") (pinfunction "A_A") (pintype "passive"))
      (node (ref "Q5") (pin "3") (pinfunction "D_3") (pintype "bidirectional"))
      (node (ref "RLA5") (pin "8") (pinfunction "A2_8") (pintype "passive"))
    )
    (net (code "56") (name "R5-SIG") (class "Default")
      (node (ref "JP14") (pin "11") (pinfunction "11_11") (pintype "passive"))
      (node (ref "Q5") (pin "1") (pinfunction "G_1") (pintype "bidirectional"))
    )
    (net (code "57") (name "R6") (class "Default")
      (node (ref "D6") (pin "A") (pinfunction "A_A") (pintype "passive"))
      (node (ref "Q6") (pin "3") (pinfunction "D_3") (pintype "bidirectional"))
      (node (ref "RLA6") (pin "8") (pinfunction "A2_8") (pintype "passive"))
    )
    (net (code "58") (name "R6-SIG") (class "Default")
      (node (ref "JP14") (pin "10") (pinfunction "10_10") (pintype "passive"))
      (node (ref "Q6") (pin "1") (pinfunction "G_1") (pintype "bidirectional"))
    )
    (net (code "59") (name "R7") (class "Default")
      (node (ref "D7") (pin "A") (pinfunction "A_A") (pintype "passive"))
      (node (ref "Q7") (pin "3") (pinfunction "D_3") (pintype "bidirectional"))
      (node (ref "RLA7") (pin "8") (pinfunction "A2_8") (pintype "passive"))
    )
    (net (code "60") (name "R7-SIG") (class "Default")
      (node (ref "JP14") (pin "9") (pinfunction "9_9") (pintype "passive"))
      (node (ref "Q7") (pin "1") (pinfunction "G_1") (pintype "bidirectional"))
    )
    (net (code "61") (name "RF2") (class "Default")
      (node (ref "C12") (pin "2") (pinfunction "P$2_2") (pintype "passive"))
      (node (ref "IC5") (pin "1") (pinfunction "P1_1") (pintype "bidirectional"))
      (node (ref "L2") (pin "1") (pinfunction "1_1") (pintype "passive"))
      (node (ref "X3") (pin "P") (pinfunction "ANT_P") (pintype "bidirectional"))
    )
    (net (code "62") (name "SCL") (class "Default")
      (node (ref "IC2") (pin "6") (pinfunction "SCL_6") (pintype "passive"))
      (node (ref "IC3") (pin "10") (pinfunction "SCL_10") (pintype "input"))
      (node (ref "JP14") (pin "5") (pinfunction "5_5") (pintype "passive"))
      (node (ref "R4") (pin "1") (pinfunction "1_1") (pintype "passive"))
    )
    (net (code "63") (name "SDA") (class "Default")
      (node (ref "IC2") (pin "7") (pinfunction "SDA_7") (pintype "passive"))
      (node (ref "IC3") (pin "9") (pinfunction "SDA_9") (pintype "bidirectional"))
      (node (ref "JP14") (pin "4") (pinfunction "4_4") (pintype "passive"))
      (node (ref "R7") (pin "1") (pinfunction "1_1") (pintype "passive"))
    )
    (net (code "64") (name "VDDA") (class "Default")
      (node (ref "C1") (pin "1") (pinfunction "P$1_1") (pintype "passive"))
      (node (ref "C2") (pin "1") (pinfunction "P$1_1") (pintype "passive"))
      (node (ref "IC1") (pin "18") (pinfunction "VDDA_18") (pintype "bidirectional"))
      (node (ref "JP16") (pin "1") (pinfunction "1_1") (pintype "passive"))
      (node (ref "JP26") (pin "2") (pinfunction "2_2") (pintype "passive"))
      (node (ref "JP28") (pin "2") (pinfunction "2_2") (pintype "passive"))
      (node (ref "RLA7") (pin "3") (pinfunction "3_3") (pintype "passive"))
    )
    (net (code "65") (name "VOK") (class "Default")
      (node (ref "IC1") (pin "8") (pinfunction "VDDD_OK_8") (pintype "bidirectional"))
      (node (ref "JP15") (pin "2") (pinfunction "2_2") (pintype "passive"))
    )
    (net (code "66") (name "unconnected-(IC2-NC-Pad13)") (class "Default")
      (node (ref "IC2") (pin "13") (pinfunction "NC_13") (pintype "passive"))
    )
    (net (code "67") (name "unconnected-(IC2-O1-Pad14)") (class "Default")
      (node (ref "IC2") (pin "14") (pinfunction "O1_14") (pintype "passive"))
    )
    (net (code "68") (name "unconnected-(IC2-O2-Pad12)") (class "Default")
      (node (ref "IC2") (pin "12") (pinfunction "O2_12") (pintype "passive"))
    )
    (net (code "69") (name "unconnected-(IC3-AIN1-Pad5)") (class "Default")
      (node (ref "IC3") (pin "5") (pinfunction "AIN1_5") (pintype "input"))
    )
    (net (code "70") (name "unconnected-(IC3-AIN2-Pad6)") (class "Default")
      (node (ref "IC3") (pin "6") (pinfunction "AIN2_6") (pintype "input"))
    )
    (net (code "71") (name "unconnected-(IC3-AIN3-Pad7)") (class "Default")
      (node (ref "IC3") (pin "7") (pinfunction "AIN3_7") (pintype "input"))
    )
    (net (code "72") (name "unconnected-(IC3-ALERT{slash}RDY-Pad2)") (class "Default")
      (node (ref "IC3") (pin "2") (pinfunction "ALERT/RDY_2") (pintype "input"))
    )
    (net (code "73") (name "unconnected-(RLA1-Pad4)") (class "Default")
      (node (ref "RLA1") (pin "4") (pinfunction "4_4") (pintype "passive"))
    )
    (net (code "74") (name "unconnected-(RLA1-Pad5)") (class "Default")
      (node (ref "RLA1") (pin "5") (pinfunction "5_5") (pintype "passive"))
    )
    (net (code "75") (name "unconnected-(RLA1-Pad6)") (class "Default")
      (node (ref "RLA1") (pin "6") (pinfunction "6_6") (pintype "passive"))
    )
    (net (code "76") (name "unconnected-(RLA1-Pad7)") (class "Default")
      (node (ref "RLA1") (pin "7") (pinfunction "7_7") (pintype "passive"))
    )
    (net (code "77") (name "unconnected-(RLA2-Pad4)") (class "Default")
      (node (ref "RLA2") (pin "4") (pinfunction "4_4") (pintype "passive"))
    )
    (net (code "78") (name "unconnected-(RLA2-Pad5)") (class "Default")
      (node (ref "RLA2") (pin "5") (pinfunction "5_5") (pintype "passive"))
    )
    (net (code "79") (name "unconnected-(RLA2-Pad6)") (class "Default")
      (node (ref "RLA2") (pin "6") (pinfunction "6_6") (pintype "passive"))
    )
    (net (code "80") (name "unconnected-(RLA2-Pad7)") (class "Default")
      (node (ref "RLA2") (pin "7") (pinfunction "7_7") (pintype "passive"))
    )
    (net (code "81") (name "unconnected-(RLA3-Pad4)") (class "Default")
      (node (ref "RLA3") (pin "4") (pinfunction "4_4") (pintype "passive"))
    )
    (net (code "82") (name "unconnected-(RLA3-Pad5)") (class "Default")
      (node (ref "RLA3") (pin "5") (pinfunction "5_5") (pintype "passive"))
    )
    (net (code "83") (name "unconnected-(RLA3-Pad6)") (class "Default")
      (node (ref "RLA3") (pin "6") (pinfunction "6_6") (pintype "passive"))
    )
    (net (code "84") (name "unconnected-(RLA3-Pad7)") (class "Default")
      (node (ref "RLA3") (pin "7") (pinfunction "7_7") (pintype "passive"))
    )
    (net (code "85") (name "unconnected-(RLA4-Pad4)") (class "Default")
      (node (ref "RLA4") (pin "4") (pinfunction "4_4") (pintype "passive"))
    )
    (net (code "86") (name "unconnected-(RLA4-Pad5)") (class "Default")
      (node (ref "RLA4") (pin "5") (pinfunction "5_5") (pintype "passive"))
    )
    (net (code "87") (name "unconnected-(RLA4-Pad6)") (class "Default")
      (node (ref "RLA4") (pin "6") (pinfunction "6_6") (pintype "passive"))
    )
    (net (code "88") (name "unconnected-(RLA4-Pad7)") (class "Default")
      (node (ref "RLA4") (pin "7") (pinfunction "7_7") (pintype "passive"))
    )
    (net (code "89") (name "unconnected-(RLA5-Pad4)") (class "Default")
      (node (ref "RLA5") (pin "4") (pinfunction "4_4") (pintype "passive"))
    )
    (net (code "90") (name "unconnected-(RLA5-Pad5)") (class "Default")
      (node (ref "RLA5") (pin "5") (pinfunction "5_5") (pintype "passive"))
    )
    (net (code "91") (name "unconnected-(RLA5-Pad6)") (class "Default")
      (node (ref "RLA5") (pin "6") (pinfunction "6_6") (pintype "passive"))
    )
    (net (code "92") (name "unconnected-(RLA5-Pad7)") (class "Default")
      (node (ref "RLA5") (pin "7") (pinfunction "7_7") (pintype "passive"))
    )
    (net (code "93") (name "unconnected-(RLA6-Pad4)") (class "Default")
      (node (ref "RLA6") (pin "4") (pinfunction "4_4") (pintype "passive"))
    )
    (net (code "94") (name "unconnected-(RLA6-Pad5)") (class "Default")
      (node (ref "RLA6") (pin "5") (pinfunction "5_5") (pintype "passive"))
    )
    (net (code "95") (name "unconnected-(RLA6-Pad6)") (class "Default")
      (node (ref "RLA6") (pin "6") (pinfunction "6_6") (pintype "passive"))
    )
    (net (code "96") (name "unconnected-(RLA6-Pad7)") (class "Default")
      (node (ref "RLA6") (pin "7") (pinfunction "7_7") (pintype "passive"))
    )
    (net (code "97") (name "unconnected-(RLA7-Pad2)") (class "Default")
      (node (ref "RLA7") (pin "2") (pinfunction "2_2") (pintype "passive"))
    )
    (net (code "98") (name "unconnected-(RLA7-Pad7)") (class "Default")
      (node (ref "RLA7") (pin "7") (pinfunction "7_7") (pintype "passive"))
    )
  )
)
